# RFID_v0_1.net
KiCad netlist of a schematic drawn in EAGLE
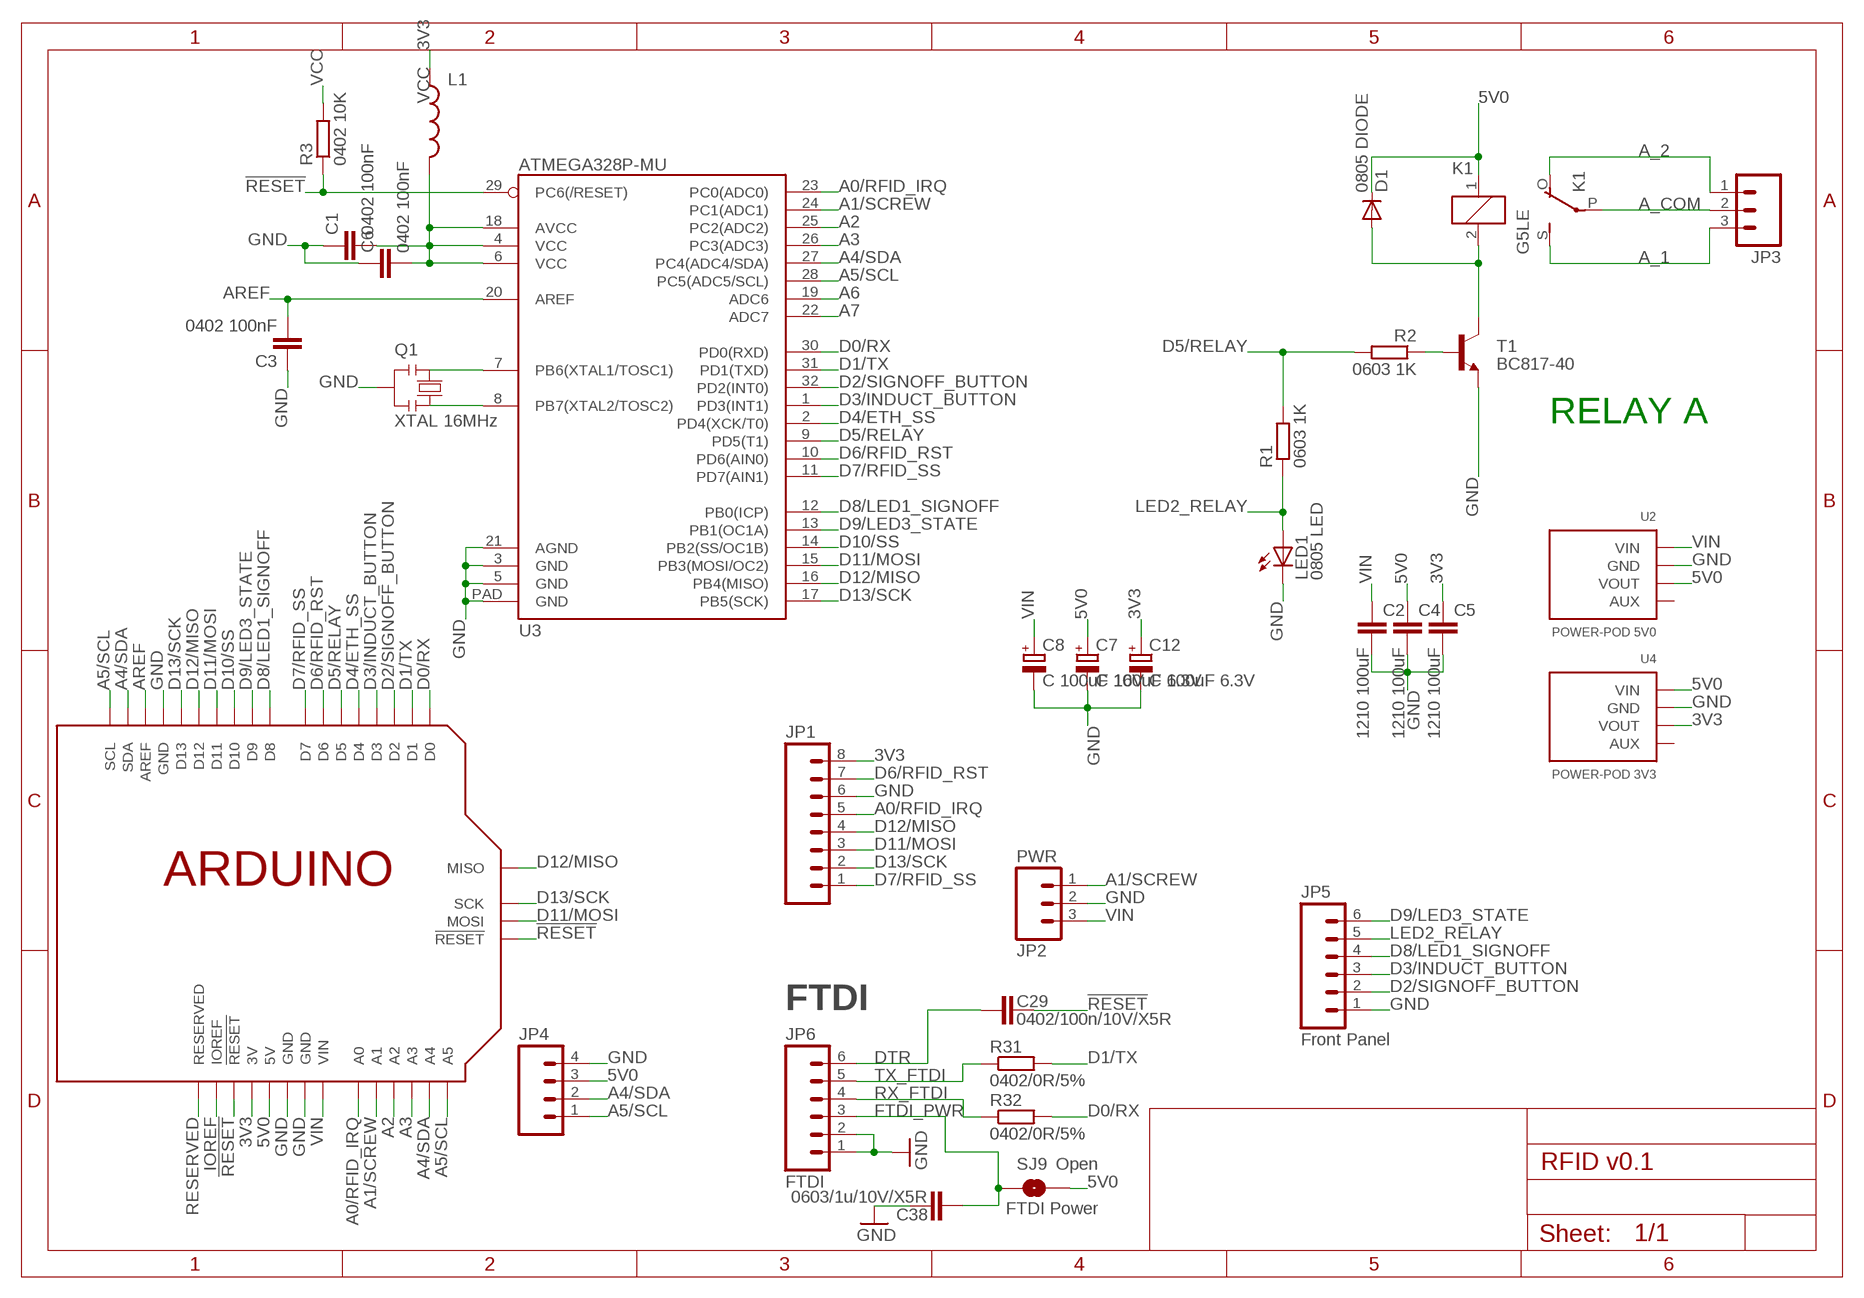
[diagram p0: schematic, sheet 1]

(export (version "E")
  (design (tool "Eeschema 10.0.6"))
  (components
    (comp (ref "C1")
      (value "0402 100nF")
      (footprint "eagle-import:C0402-SMALLER")
      (libsource (lib "eagle-import") (part "C-EUC0402-SMALLER"))
    )
    (comp (ref "C2")
      (value "1210 100uF")
      (footprint "eagle-import:C1210")
      (libsource (lib "eagle-import") (part "C-EUC1210"))
    )
    (comp (ref "C3")
      (value "0402 100nF")
      (footprint "eagle-import:C0402-SMALLER")
      (libsource (lib "eagle-import") (part "C-EUC0402-SMALLER"))
    )
    (comp (ref "C4")
      (value "1210 100uF")
      (footprint "eagle-import:C1210")
      (libsource (lib "eagle-import") (part "C-EUC1210"))
    )
    (comp (ref "C5")
      (value "1210 100uF")
      (footprint "eagle-import:C1210")
      (libsource (lib "eagle-import") (part "C-EUC1210"))
    )
    (comp (ref "C6")
      (value "0402 100nF")
      (footprint "eagle-import:C0402-SMALLER")
      (libsource (lib "eagle-import") (part "C-EUC0402-SMALLER"))
    )
    (comp (ref "C7")
      (value "C 100uF 6.3V")
      (footprint "eagle-import:PANASONIC_C")
      (libsource (lib "eagle-import") (part "CPOL-EUC"))
    )
    (comp (ref "C8")
      (value "C 100uF 16V")
      (footprint "eagle-import:PANASONIC_C")
      (libsource (lib "eagle-import") (part "CPOL-EUC"))
    )
    (comp (ref "C12")
      (value "C 100uF 6.3V")
      (footprint "eagle-import:PANASONIC_C")
      (libsource (lib "eagle-import") (part "CPOL-EUC"))
    )
    (comp (ref "C29")
      (value "0402/100n/10V/X5R")
      (footprint "eagle-import:C0402-ARDUINO-ROUND")
      (libsource (lib "eagle-import") (part "TiLDA Mk2 Parts_C-EUC0402-ARDUINO-ROUND"))
    )
    (comp (ref "C38")
      (value "0603/1u/10V/X5R")
      (footprint "eagle-import:C0603-ROUND")
      (libsource (lib "eagle-import") (part "TiLDA Mk2 Parts_C-EUC0603-ROUND"))
    )
    (comp (ref "D1")
      (value "0805 DIODE")
      (footprint "eagle-import:0805-DIODE")
      (libsource (lib "eagle-import") (part "DIODE-0805"))
    )
    (comp (ref "JP1")
      (value "M081X08")
      (footprint "eagle-import:1X08")
      (libsource (lib "eagle-import") (part "M081X08"))
    )
    (comp (ref "JP2")
      (value "PWR")
      (footprint "eagle-import:SCREWTERMINAL-5MM-3")
      (libsource (lib "eagle-import") (part "M03-SCREW-5MM"))
    )
    (comp (ref "JP3")
      (value "M03-SCREW-5MM")
      (footprint "eagle-import:SCREWTERMINAL-5MM-3")
      (libsource (lib "eagle-import") (part "M03-SCREW-5MM"))
    )
    (comp (ref "JP4")
      (value "M04PTH")
      (footprint "eagle-import:1X04")
      (libsource (lib "eagle-import") (part "M04PTH"))
    )
    (comp (ref "JP5")
      (value "Front Panel")
      (footprint "eagle-import:1X06")
      (libsource (lib "eagle-import") (part "M06SIP"))
    )
    (comp (ref "JP6")
      (value "FTDI")
      (footprint "eagle-import:1X06")
      (libsource (lib "eagle-import") (part "M06SIP"))
    )
    (comp (ref "K1")
      (value "G5LE")
      (footprint "eagle-import:G5LE")
      (libsource (lib "eagle-import") (part "G5LE"))
    )
    (comp (ref "L1")
      (value "INDUCTOR0603K-SMALL")
      (footprint "eagle-import:C0603K-SMALL")
      (libsource (lib "eagle-import") (part "INDUCTOR0603K-SMALL"))
    )
    (comp (ref "LED1")
      (value "0805 LED")
      (footprint "eagle-import:LED-0805-1206")
      (libsource (lib "eagle-import") (part "LED0805-1206"))
    )
    (comp (ref "Q1")
      (value "XTAL 16MHz")
      (footprint "eagle-import:RESONATOR")
      (libsource (lib "eagle-import") (part "RESONATORMU"))
    )
    (comp (ref "R1")
      (value "0603 1K")
      (footprint "eagle-import:C0603K-SMALL")
      (libsource (lib "eagle-import") (part "R-EU_0603K-SMALL"))
    )
    (comp (ref "R2")
      (value "0603 1K")
      (footprint "eagle-import:C0603K-SMALL")
      (libsource (lib "eagle-import") (part "R-EU_0603K-SMALL"))
    )
    (comp (ref "R3")
      (value "0402 10K")
      (footprint "eagle-import:R0402-SMALLER")
      (libsource (lib "eagle-import") (part "R-EU_R0402-SMALLER"))
    )
    (comp (ref "R31")
      (value "0402/0R/5%")
      (footprint "eagle-import:R0402-ARDUINO-ROUND")
      (libsource (lib "eagle-import") (part "R-EU_R0402-ARDUINO-ROUND"))
    )
    (comp (ref "R32")
      (value "0402/0R/5%")
      (footprint "eagle-import:R0402-ARDUINO-ROUND")
      (libsource (lib "eagle-import") (part "R-EU_R0402-ARDUINO-ROUND"))
    )
    (comp (ref "SJ9")
      (value "FTDI Power")
      (footprint "eagle-import:SJ_2S-NO")
      (libsource (lib "eagle-import") (part "SOLDERJUMPERNO"))
    )
    (comp (ref "T1")
      (value "BC817-40")
      (footprint "eagle-import:SOT23-BEC")
      (libsource (lib "eagle-import") (part "-NPN-SOT23-BECBC817"))
    )
    (comp (ref "U1")
      (value "ARDUINOSPI-REFRENCE")
      (footprint "eagle-import:ARDUINOR3-LWKTXT-REF-SPI")
      (libsource (lib "eagle-import") (part "ARDUINOSPI-REFRENCE"))
    )
    (comp (ref "U2")
      (value "POWER-POD 5V0")
      (footprint "eagle-import:POWER-POD-LANDING")
      (libsource (lib "eagle-import") (part "POWER-POD"))
    )
    (comp (ref "U3")
      (value "ATMEGA328P-MU")
      (footprint "eagle-import:MLF32-SHORT-CREAM")
      (libsource (lib "eagle-import") (part "ATMEGA328-MLF-SHORT"))
    )
    (comp (ref "U4")
      (value "POWER-POD 3V3")
      (footprint "eagle-import:POWER-POD-LANDING")
      (libsource (lib "eagle-import") (part "POWER-POD"))
    )
  )
  (nets
    (net (code "1") (name "/3V3") (class "Default")
      (node (ref "C12") (pin "+") (pinfunction "+_+") (pintype "passive"))
      (node (ref "C5") (pin "1") (pinfunction "1_1") (pintype "passive"))
      (node (ref "JP1") (pin "8") (pinfunction "8_8") (pintype "passive"))
      (node (ref "L1") (pin "1") (pinfunction "1_1") (pintype "passive"))
      (node (ref "U1") (pin "3V") (pinfunction "3V_3V") (pintype "power_in"))
      (node (ref "U4") (pin "3") (pinfunction "VOUT_3") (pintype "bidirectional"))
    )
    (net (code "2") (name "/5V0") (class "Default")
      (node (ref "C4") (pin "1") (pinfunction "1_1") (pintype "passive"))
      (node (ref "C7") (pin "+") (pinfunction "+_+") (pintype "passive"))
      (node (ref "D1") (pin "C") (pinfunction "C_C") (pintype "passive"))
      (node (ref "JP4") (pin "3") (pinfunction "3_3") (pintype "passive"))
      (node (ref "K1") (pin "1") (pinfunction "1_1") (pintype "passive"))
      (node (ref "SJ9") (pin "2") (pinfunction "2_2") (pintype "passive"))
      (node (ref "U1") (pin "5V") (pinfunction "5V_5V") (pintype "power_in"))
      (node (ref "U1") (pin "5V@ISP") (pinfunction "5V_5V@ISP") (pintype "power_in"))
      (node (ref "U2") (pin "3") (pinfunction "VOUT_3") (pintype "bidirectional"))
      (node (ref "U4") (pin "1") (pinfunction "VIN_1") (pintype "bidirectional"))
    )
    (net (code "3") (name "/A0{slash}RFID_IRQ") (class "Default")
      (node (ref "JP1") (pin "5") (pinfunction "5_5") (pintype "passive"))
      (node (ref "U1") (pin "A0") (pinfunction "A0_A0") (pintype "bidirectional"))
      (node (ref "U3") (pin "23") (pinfunction "PC0(ADC0)_23") (pintype "bidirectional"))
    )
    (net (code "4") (name "/A1{slash}SCREW") (class "Default")
      (node (ref "JP2") (pin "1") (pinfunction "1_1") (pintype "passive"))
      (node (ref "U1") (pin "A1") (pinfunction "A1_A1") (pintype "bidirectional"))
      (node (ref "U3") (pin "24") (pinfunction "PC1(ADC1)_24") (pintype "bidirectional"))
    )
    (net (code "5") (name "/A2") (class "Default")
      (node (ref "U1") (pin "A2") (pinfunction "A2_A2") (pintype "bidirectional"))
      (node (ref "U3") (pin "25") (pinfunction "PC2(ADC2)_25") (pintype "bidirectional"))
    )
    (net (code "6") (name "/A3") (class "Default")
      (node (ref "U1") (pin "A3") (pinfunction "A3_A3") (pintype "bidirectional"))
      (node (ref "U3") (pin "26") (pinfunction "PC3(ADC3)_26") (pintype "bidirectional"))
    )
    (net (code "7") (name "/A4{slash}SDA") (class "Default")
      (node (ref "JP4") (pin "2") (pinfunction "2_2") (pintype "passive"))
      (node (ref "U1") (pin "A4") (pinfunction "A4_A4") (pintype "bidirectional"))
      (node (ref "U1") (pin "SDA") (pinfunction "SDA_SDA") (pintype "bidirectional"))
      (node (ref "U3") (pin "27") (pinfunction "PC4(ADC4/SDA)_27") (pintype "bidirectional"))
    )
    (net (code "8") (name "/A5{slash}SCL") (class "Default")
      (node (ref "JP4") (pin "1") (pinfunction "1_1") (pintype "passive"))
      (node (ref "U1") (pin "A5") (pinfunction "A5_A5") (pintype "bidirectional"))
      (node (ref "U1") (pin "SCL") (pinfunction "SCL_SCL") (pintype "bidirectional"))
      (node (ref "U3") (pin "28") (pinfunction "PC5(ADC5/SCL)_28") (pintype "bidirectional"))
    )
    (net (code "9") (name "/A6") (class "Default")
      (node (ref "U3") (pin "19") (pinfunction "ADC6_19") (pintype "bidirectional"))
    )
    (net (code "10") (name "/A7") (class "Default")
      (node (ref "U3") (pin "22") (pinfunction "ADC7_22") (pintype "bidirectional"))
    )
    (net (code "11") (name "/AREF") (class "Default")
      (node (ref "C3") (pin "2") (pinfunction "2_2") (pintype "passive"))
      (node (ref "U1") (pin "AREF") (pinfunction "AREF_AREF") (pintype "bidirectional"))
      (node (ref "U3") (pin "20") (pinfunction "AREF_20") (pintype "bidirectional"))
    )
    (net (code "12") (name "/A_1") (class "Default")
      (node (ref "JP3") (pin "3") (pinfunction "3_3") (pintype "passive"))
      (node (ref "K1") (pin "S") (pinfunction "S_S") (pintype "passive"))
    )
    (net (code "13") (name "/A_2") (class "Default")
      (node (ref "JP3") (pin "1") (pinfunction "1_1") (pintype "passive"))
      (node (ref "K1") (pin "O") (pinfunction "O_O") (pintype "passive"))
    )
    (net (code "14") (name "/A_COM") (class "Default")
      (node (ref "JP3") (pin "2") (pinfunction "2_2") (pintype "passive"))
      (node (ref "K1") (pin "P") (pinfunction "P_P") (pintype "passive"))
    )
    (net (code "15") (name "/D0{slash}RX") (class "Default")
      (node (ref "R32") (pin "2") (pinfunction "2_2") (pintype "passive"))
      (node (ref "U1") (pin "D0") (pinfunction "D0_D0") (pintype "bidirectional"))
      (node (ref "U3") (pin "30") (pinfunction "PD0(RXD)_30") (pintype "bidirectional"))
    )
    (net (code "16") (name "/D1{slash}TX") (class "Default")
      (node (ref "R31") (pin "2") (pinfunction "2_2") (pintype "passive"))
      (node (ref "U1") (pin "D1") (pinfunction "D1_D1") (pintype "bidirectional"))
      (node (ref "U3") (pin "31") (pinfunction "PD1(TXD)_31") (pintype "bidirectional"))
    )
    (net (code "17") (name "/D2{slash}SIGNOFF_BUTTON") (class "Default")
      (node (ref "JP5") (pin "2") (pinfunction "2_2") (pintype "passive"))
      (node (ref "U1") (pin "D2") (pinfunction "D2_D2") (pintype "bidirectional"))
      (node (ref "U3") (pin "32") (pinfunction "PD2(INT0)_32") (pintype "bidirectional"))
    )
    (net (code "18") (name "/D3{slash}INDUCT_BUTTON") (class "Default")
      (node (ref "JP5") (pin "3") (pinfunction "3_3") (pintype "passive"))
      (node (ref "U1") (pin "D3") (pinfunction "D3_D3") (pintype "bidirectional"))
      (node (ref "U3") (pin "1") (pinfunction "PD3(INT1)_1") (pintype "bidirectional"))
    )
    (net (code "19") (name "/D4{slash}ETH_SS") (class "Default")
      (node (ref "U1") (pin "D4") (pinfunction "D4_D4") (pintype "bidirectional"))
      (node (ref "U3") (pin "2") (pinfunction "PD4(XCK/T0)_2") (pintype "bidirectional"))
    )
    (net (code "20") (name "/D5{slash}RELAY") (class "Default")
      (node (ref "R1") (pin "2") (pinfunction "2_2") (pintype "passive"))
      (node (ref "R2") (pin "2") (pinfunction "2_2") (pintype "passive"))
      (node (ref "U1") (pin "D5") (pinfunction "D5_D5") (pintype "bidirectional"))
      (node (ref "U3") (pin "9") (pinfunction "PD5(T1)_9") (pintype "bidirectional"))
    )
    (net (code "21") (name "/D6{slash}RFID_RST") (class "Default")
      (node (ref "JP1") (pin "7") (pinfunction "7_7") (pintype "passive"))
      (node (ref "U1") (pin "D6") (pinfunction "D6_D6") (pintype "bidirectional"))
      (node (ref "U3") (pin "10") (pinfunction "PD6(AIN0)_10") (pintype "bidirectional"))
    )
    (net (code "22") (name "/D7{slash}RFID_SS") (class "Default")
      (node (ref "JP1") (pin "1") (pinfunction "1_1") (pintype "passive"))
      (node (ref "U1") (pin "D7") (pinfunction "D7_D7") (pintype "bidirectional"))
      (node (ref "U3") (pin "11") (pinfunction "PD7(AIN1)_11") (pintype "bidirectional"))
    )
    (net (code "23") (name "/D8{slash}LED1_SIGNOFF") (class "Default")
      (node (ref "JP5") (pin "4") (pinfunction "4_4") (pintype "passive"))
      (node (ref "U1") (pin "D8") (pinfunction "D8_D8") (pintype "bidirectional"))
      (node (ref "U3") (pin "12") (pinfunction "PB0(ICP)_12") (pintype "bidirectional"))
    )
    (net (code "24") (name "/D9{slash}LED3_STATE") (class "Default")
      (node (ref "JP5") (pin "6") (pinfunction "6_6") (pintype "passive"))
      (node (ref "U1") (pin "D9") (pinfunction "D9_D9") (pintype "bidirectional"))
      (node (ref "U3") (pin "13") (pinfunction "PB1(OC1A)_13") (pintype "bidirectional"))
    )
    (net (code "25") (name "/D10{slash}SS") (class "Default")
      (node (ref "U1") (pin "D10") (pinfunction "D10_D10") (pintype "bidirectional"))
      (node (ref "U3") (pin "14") (pinfunction "PB2(SS/OC1B)_14") (pintype "bidirectional"))
    )
    (net (code "26") (name "/D11{slash}MOSI") (class "Default")
      (node (ref "JP1") (pin "3") (pinfunction "3_3") (pintype "passive"))
      (node (ref "U1") (pin "D11") (pinfunction "D11_D11") (pintype "bidirectional"))
      (node (ref "U1") (pin "MOSI") (pinfunction "MOSI_MOSI") (pintype "bidirectional"))
      (node (ref "U3") (pin "15") (pinfunction "PB3(MOSI/OC2)_15") (pintype "bidirectional"))
    )
    (net (code "27") (name "/D12{slash}MISO") (class "Default")
      (node (ref "JP1") (pin "4") (pinfunction "4_4") (pintype "passive"))
      (node (ref "U1") (pin "D12") (pinfunction "D12_D12") (pintype "bidirectional"))
      (node (ref "U1") (pin "MISO") (pinfunction "MISO_MISO") (pintype "bidirectional"))
      (node (ref "U3") (pin "16") (pinfunction "PB4(MISO)_16") (pintype "bidirectional"))
    )
    (net (code "28") (name "/D13{slash}SCK") (class "Default")
      (node (ref "JP1") (pin "2") (pinfunction "2_2") (pintype "passive"))
      (node (ref "U1") (pin "D13") (pinfunction "D13_D13") (pintype "bidirectional"))
      (node (ref "U1") (pin "SCK") (pinfunction "SCK_SCK") (pintype "bidirectional"))
      (node (ref "U3") (pin "17") (pinfunction "PB5(SCK)_17") (pintype "bidirectional"))
    )
    (net (code "29") (name "/DTR") (class "Default")
      (node (ref "C29") (pin "2") (pinfunction "2_2") (pintype "passive"))
      (node (ref "JP6") (pin "6") (pinfunction "6_6") (pintype "passive"))
    )
    (net (code "30") (name "/FTDI_PWR") (class "Default")
      (node (ref "C38") (pin "2") (pinfunction "2_2") (pintype "passive"))
      (node (ref "JP6") (pin "3") (pinfunction "3_3") (pintype "passive"))
      (node (ref "SJ9") (pin "1") (pinfunction "1_1") (pintype "passive"))
    )
    (net (code "31") (name "/IOREF") (class "Default")
      (node (ref "U1") (pin "IOREF") (pinfunction "IOREF_IOREF") (pintype "output"))
    )
    (net (code "32") (name "/LED2_RELAY") (class "Default")
      (node (ref "JP5") (pin "5") (pinfunction "5_5") (pintype "passive"))
      (node (ref "LED1") (pin "A") (pinfunction "A_A") (pintype "passive"))
      (node (ref "R1") (pin "1") (pinfunction "1_1") (pintype "passive"))
    )
    (net (code "34") (name "/RX_FTDI") (class "Default")
      (node (ref "JP6") (pin "4") (pinfunction "4_4") (pintype "passive"))
      (node (ref "R32") (pin "1") (pinfunction "1_1") (pintype "passive"))
    )
    (net (code "35") (name "/TX_FTDI") (class "Default")
      (node (ref "JP6") (pin "5") (pinfunction "5_5") (pintype "passive"))
      (node (ref "R31") (pin "1") (pinfunction "1_1") (pintype "passive"))
    )
    (net (code "36") (name "/VCC") (class "Default")
      (node (ref "C1") (pin "2") (pinfunction "2_2") (pintype "passive"))
      (node (ref "C6") (pin "2") (pinfunction "2_2") (pintype "passive"))
      (node (ref "L1") (pin "2") (pinfunction "2_2") (pintype "passive"))
      (node (ref "R3") (pin "2") (pinfunction "2_2") (pintype "passive"))
      (node (ref "U3") (pin "18") (pinfunction "AVCC_18") (pintype "bidirectional"))
      (node (ref "U3") (pin "4") (pinfunction "VCC_4") (pintype "bidirectional"))
      (node (ref "U3") (pin "6") (pinfunction "VCC_6") (pintype "bidirectional"))
    )
    (net (code "37") (name "/VIN") (class "Default")
      (node (ref "C2") (pin "1") (pinfunction "1_1") (pintype "passive"))
      (node (ref "C8") (pin "+") (pinfunction "+_+") (pintype "passive"))
      (node (ref "JP2") (pin "3") (pinfunction "3_3") (pintype "passive"))
      (node (ref "U1") (pin "VIN") (pinfunction "VIN_VIN") (pintype "power_in"))
      (node (ref "U2") (pin "1") (pinfunction "VIN_1") (pintype "bidirectional"))
    )
    (net (code "38") (name "/~{RESET}") (class "Default")
      (node (ref "C29") (pin "1") (pinfunction "1_1") (pintype "passive"))
      (node (ref "R3") (pin "1") (pinfunction "1_1") (pintype "passive"))
      (node (ref "U1") (pin "!RESET") (pinfunction "~{RESET}_!RESET") (pintype "bidirectional"))
      (node (ref "U1") (pin "!RESET@ISP") (pinfunction "~{RESET}_!RESET@ISP") (pintype "bidirectional"))
      (node (ref "U3") (pin "29") (pinfunction "PC6(/RESET)_29") (pintype "bidirectional"))
    )
    (net (code "39") (name "GND") (class "Default")
      (node (ref "C1") (pin "1") (pinfunction "1_1") (pintype "passive"))
      (node (ref "C12") (pin "-") (pinfunction "-_-") (pintype "passive"))
      (node (ref "C2") (pin "2") (pinfunction "2_2") (pintype "passive"))
      (node (ref "C3") (pin "1") (pinfunction "1_1") (pintype "passive"))
      (node (ref "C38") (pin "1") (pinfunction "1_1") (pintype "passive"))
      (node (ref "C4") (pin "2") (pinfunction "2_2") (pintype "passive"))
      (node (ref "C5") (pin "2") (pinfunction "2_2") (pintype "passive"))
      (node (ref "C6") (pin "1") (pinfunction "1_1") (pintype "passive"))
      (node (ref "C7") (pin "-") (pinfunction "-_-") (pintype "passive"))
      (node (ref "C8") (pin "-") (pinfunction "-_-") (pintype "passive"))
      (node (ref "JP1") (pin "6") (pinfunction "6_6") (pintype "passive"))
      (node (ref "JP2") (pin "2") (pinfunction "2_2") (pintype "passive"))
      (node (ref "JP4") (pin "4") (pinfunction "4_4") (pintype "passive"))
      (node (ref "JP5") (pin "1") (pinfunction "1_1") (pintype "passive"))
      (node (ref "JP6") (pin "1") (pinfunction "1_1") (pintype "passive"))
      (node (ref "JP6") (pin "2") (pinfunction "2_2") (pintype "passive"))
      (node (ref "LED1") (pin "C") (pinfunction "C_C") (pintype "passive"))
      (node (ref "Q1") (pin "2") (pinfunction "2_2") (pintype "passive"))
      (node (ref "T1") (pin "E") (pinfunction "E_E") (pintype "passive"))
      (node (ref "U1") (pin "GND@1") (pinfunction "GND_GND@1") (pintype "power_in"))
      (node (ref "U1") (pin "GND@2") (pinfunction "GND_GND@2") (pintype "power_in"))
      (node (ref "U1") (pin "GND@3") (pinfunction "GND_GND@3") (pintype "power_in"))
      (node (ref "U1") (pin "GND@ISP") (pinfunction "GND_GND@ISP") (pintype "power_in"))
      (node (ref "U2") (pin "2") (pinfunction "GND_2") (pintype "bidirectional"))
      (node (ref "U3") (pin "21") (pinfunction "AGND_21") (pintype "bidirectional"))
      (node (ref "U3") (pin "3") (pinfunction "GND_3") (pintype "bidirectional"))
      (node (ref "U3") (pin "5") (pinfunction "GND_5") (pintype "bidirectional"))
      (node (ref "U3") (pin "PAD") (pinfunction "GND_PAD") (pintype "bidirectional"))
      (node (ref "U4") (pin "2") (pinfunction "GND_2") (pintype "bidirectional"))
    )
    (net (code "40") (name "Net-(D1-PadA)") (class "Default")
      (node (ref "D1") (pin "A") (pinfunction "A_A") (pintype "passive"))
      (node (ref "K1") (pin "2") (pinfunction "2_2") (pintype "passive"))
      (node (ref "T1") (pin "C") (pinfunction "C_C") (pintype "passive"))
    )
    (net (code "41") (name "Net-(R2-Pad1)") (class "Default")
      (node (ref "R2") (pin "1") (pinfunction "1_1") (pintype "passive"))
      (node (ref "T1") (pin "B") (pinfunction "B_B") (pintype "passive"))
    )
    (net (code "42") (name "Net-(U3-PB6(XTAL1{slash}TOSC1))") (class "Default")
      (node (ref "Q1") (pin "1") (pinfunction "1_1") (pintype "passive"))
      (node (ref "U3") (pin "7") (pinfunction "PB6(XTAL1/TOSC1)_7") (pintype "bidirectional"))
    )
    (net (code "43") (name "Net-(U3-PB7(XTAL2{slash}TOSC2))") (class "Default")
      (node (ref "Q1") (pin "3") (pinfunction "3_3") (pintype "passive"))
      (node (ref "U3") (pin "8") (pinfunction "PB7(XTAL2/TOSC2)_8") (pintype "bidirectional"))
    )
    (net (code "44") (name "unconnected-(U1-PadRESERVED)") (class "Default")
      (node (ref "U1") (pin "RESERVED") (pinfunction "RESERVED_RESERVED") (pintype "no_connect"))
    )
    (net (code "45") (name "unconnected-(U2-AUX-Pad4)") (class "Default")
      (node (ref "U2") (pin "4") (pinfunction "AUX_4") (pintype "bidirectional"))
    )
    (net (code "46") (name "unconnected-(U4-AUX-Pad4)") (class "Default")
      (node (ref "U4") (pin "4") (pinfunction "AUX_4") (pintype "bidirectional"))
    )
  )
)
